# sensors.net
KiCad netlist of a schematic drawn in Altium Designer
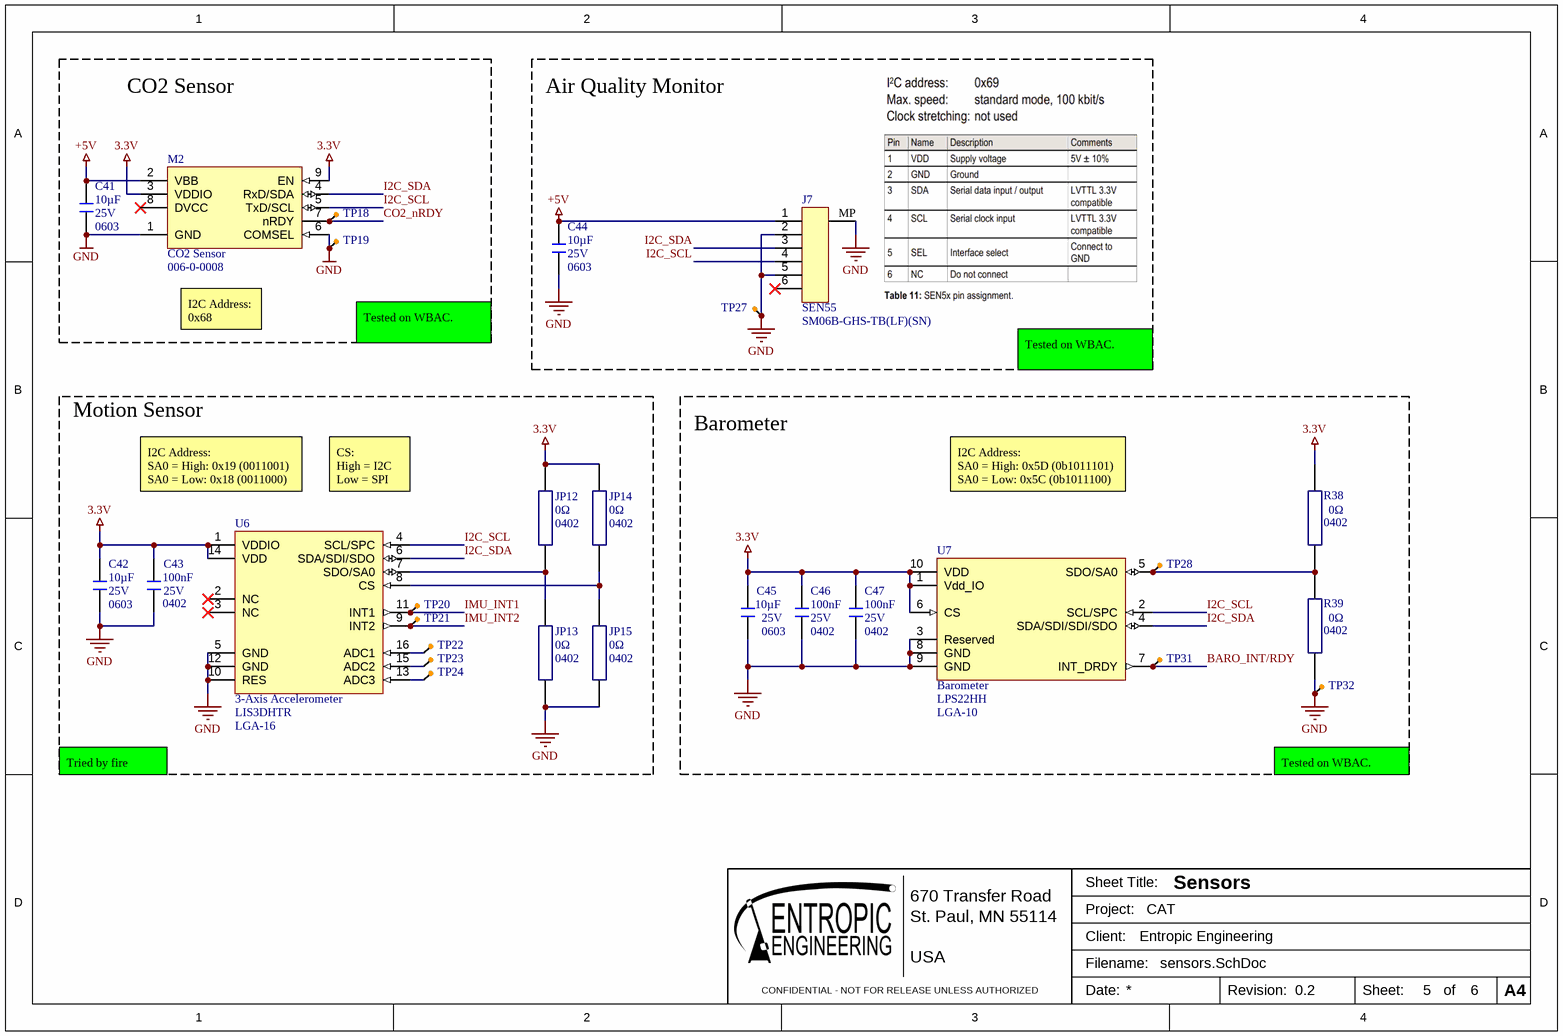
[diagram p0: sensors.SchDoc]

(export (version "E")
  (design (tool "Eeschema 10.0.6"))
  (components
    (comp (ref "C41")
      (value "10µF")
      (footprint "0603_capacitor")
      (description "10 µF, 25 V, X5R, 0603 Chip capacitor")
      (fields
        (field (name "MANUFACTURER") "Samsung")
        (field (name "CASE/PACKAGE") "0603")
        (field (name "TOLERANCE") "20%")
        (field (name "VOLTAGE RATING") "25V")
      )
      (libsource (lib "cat") (part "CL10A106MA8NRNC"))
    )
    (comp (ref "C42")
      (value "10µF")
      (footprint "0603_capacitor")
      (description "10 µF, 25 V, X5R, 0603 Chip capacitor")
      (fields
        (field (name "MANUFACTURER") "Samsung")
        (field (name "CASE/PACKAGE") "0603")
        (field (name "TOLERANCE") "20%")
        (field (name "VOLTAGE RATING") "25V")
      )
      (libsource (lib "cat") (part "CL10A106MA8NRNC"))
    )
    (comp (ref "C43")
      (value "GRM155R71E104KE14D")
      (footprint "0402_capacitor")
      (description "100 nF, 25 V, X7R, 0402 Chip capacitor")
      (fields
        (field (name "MANUFACTURER") "Murata")
        (field (name "TOLERANCE") "10%")
        (field (name "CASE CODE (IMPERIAL)") "0402")
        (field (name "VOLTAGE") "25V")
        (field (name "CAPACITANCE") "100nF")
      )
      (libsource (lib "cat") (part "GRM155R71E104KE14D"))
    )
    (comp (ref "C44")
      (value "10µF")
      (footprint "0603_capacitor")
      (description "10 µF, 25 V, X5R, 0603 Chip capacitor")
      (fields
        (field (name "MANUFACTURER") "Samsung")
        (field (name "CASE/PACKAGE") "0603")
        (field (name "TOLERANCE") "20%")
        (field (name "VOLTAGE RATING") "25V")
      )
      (libsource (lib "cat") (part "CL10A106MA8NRNC"))
    )
    (comp (ref "C45")
      (value "10µF")
      (footprint "0603_capacitor")
      (description "10 µF, 25 V, X5R, 0603 Chip capacitor")
      (fields
        (field (name "MANUFACTURER") "Samsung")
        (field (name "MANUFACTURER PART NUMBER") "CL10A106MA8NRNC")
        (field (name "VOLTAGE RATING") "25V")
        (field (name "CASE/PACKAGE") "0603")
      )
      (libsource (lib "cat") (part "CL10A106MA8NRNC"))
    )
    (comp (ref "C46")
      (value "GRM155R71E104KE14D")
      (footprint "0402_capacitor")
      (description "100 nF, 25 V, X7R, 0402 Chip capacitor")
      (fields
        (field (name "MANUFACTURER") "Murata")
        (field (name "TOLERANCE") "10%")
        (field (name "CASE CODE (IMPERIAL)") "0402")
        (field (name "VOLTAGE") "25V")
        (field (name "CAPACITANCE") "100nF")
      )
      (libsource (lib "cat") (part "GRM155R71E104KE14D"))
    )
    (comp (ref "C47")
      (value "GRM155R71E104KE14D")
      (footprint "0402_capacitor")
      (description "100 nF, 25 V, X7R, 0402 Chip capacitor")
      (fields
        (field (name "MANUFACTURER") "Murata")
        (field (name "TOLERANCE") "10%")
        (field (name "CASE CODE (IMPERIAL)") "0402")
        (field (name "VOLTAGE") "25V")
        (field (name "CAPACITANCE") "100nF")
      )
      (libsource (lib "cat") (part "GRM155R71E104KE14D"))
    )
    (comp (ref "J7")
      (value "SEN55")
      (footprint "SM06B-GHS-TB")
      (description "6-Pin JST GH header, 1.25mm pitch, SMD right angle")
      (fields
        (field (name "MANUFACTURER") "JST")
        (field (name "MANUFACTURER PART NUMBER") "SM06B-GHS-TB(LF)(SN)")
      )
      (libsource (lib "cat") (part "SM06B-GHS-TB(LF)(SN)"))
    )
    (comp (ref "JP12")
      (value "0Ω")
      (footprint "0402_resistor")
      (description "0 Ω, 0402 Chip resistor (jumper)")
      (fields
        (field (name "MANUFACTURER") "Yageo")
        (field (name "MANUFACTURER PART NUMBER") "RC0402FR-070RL")
        (field (name "CASE/PACKAGE") "0402")
      )
      (libsource (lib "cat") (part "RC0402FR-070RL"))
    )
    (comp (ref "JP13")
      (value "0Ω")
      (footprint "0402_resistor")
      (description "0 Ω, 0402 Chip resistor (jumper)")
      (fields
        (field (name "MANUFACTURER") "Yageo")
        (field (name "MANUFACTURER PART NUMBER") "RC0402FR-070RL")
        (field (name "CASE/PACKAGE") "0402")
      )
      (libsource (lib "cat") (part "RC0402FR-070RL"))
    )
    (comp (ref "JP14")
      (value "0Ω")
      (footprint "0402_resistor")
      (description "0 Ω, 0402 Chip resistor (jumper)")
      (fields
        (field (name "MANUFACTURER") "Yageo")
        (field (name "MANUFACTURER PART NUMBER") "RC0402FR-070RL")
        (field (name "CASE/PACKAGE") "0402")
      )
      (libsource (lib "cat") (part "RC0402FR-070RL"))
    )
    (comp (ref "JP15")
      (value "0Ω")
      (footprint "0402_resistor")
      (description "0 Ω, 0402 Chip resistor (jumper)")
      (fields
        (field (name "MANUFACTURER") "Yageo")
        (field (name "MANUFACTURER PART NUMBER") "RC0402FR-070RL")
        (field (name "CASE/PACKAGE") "0402")
      )
      (libsource (lib "cat") (part "RC0402FR-070RL"))
    )
    (comp (ref "M2")
      (value "CO2 Sensor")
      (footprint "006-0-0008")
      (description "Sensair CO2 sensor")
      (fields (field (name "MANUFACTURER PART NUMBER") "006-0-0008"))
      (libsource (lib "cat") (part "006-0-0008"))
    )
    (comp (ref "R38")
      (value "0Ω")
      (footprint "0402_resistor")
      (description "0 Ω, 0402 Chip resistor (jumper)")
      (fields
        (field (name "MANUFACTURER") "Yageo")
        (field (name "MANUFACTURER PART NUMBER") "RC0402FR-070RL")
        (field (name "CASE/PACKAGE") "0402")
      )
      (libsource (lib "cat") (part "RC0402FR-070RL"))
    )
    (comp (ref "R39")
      (value "0Ω")
      (footprint "0402_resistor")
      (description "0 Ω, 0402 Chip resistor (jumper)")
      (fields
        (field (name "MANUFACTURER") "Yageo")
        (field (name "MANUFACTURER PART NUMBER") "RC0402FR-070RL")
        (field (name "CASE/PACKAGE") "0402")
      )
      (libsource (lib "cat") (part "RC0402FR-070RL"))
    )
    (comp (ref "TP18")
      (value "CO2_nRDY")
      (footprint "test_point-1")
      (description "Test point")
      (libsource (lib "cat") (part "test_point-1"))
    )
    (comp (ref "TP19")
      (value "SENSOR_SDA")
      (footprint "test_point-1")
      (description "Test point")
      (libsource (lib "cat") (part "test_point-1"))
    )
    (comp (ref "TP20")
      (value "test_point-1")
      (footprint "test_point-1")
      (description "Test point")
      (libsource (lib "cat") (part "test_point-1"))
    )
    (comp (ref "TP21")
      (value "test_point-1")
      (footprint "test_point-1")
      (description "Test point")
      (libsource (lib "cat") (part "test_point-1"))
    )
    (comp (ref "TP22")
      (value "test_point-1")
      (footprint "test_point-1")
      (description "Test point")
      (libsource (lib "cat") (part "test_point-1"))
    )
    (comp (ref "TP23")
      (value "test_point-1")
      (footprint "test_point-1")
      (description "Test point")
      (libsource (lib "cat") (part "test_point-1"))
    )
    (comp (ref "TP24")
      (value "test_point-1")
      (footprint "test_point-1")
      (description "Test point")
      (libsource (lib "cat") (part "test_point-1"))
    )
    (comp (ref "TP27")
      (value "SENSOR_SDA")
      (footprint "test_point-1")
      (description "Test point")
      (libsource (lib "cat") (part "test_point-1"))
    )
    (comp (ref "TP28")
      (value "SENSOR_SDA")
      (footprint "test_point-1")
      (description "Test point")
      (libsource (lib "cat") (part "test_point-1"))
    )
    (comp (ref "TP31")
      (value "SENSOR_SCL")
      (footprint "test_point-1")
      (description "Test point")
      (libsource (lib "cat") (part "test_point-1"))
    )
    (comp (ref "TP32")
      (value "SENSOR_SDA")
      (footprint "test_point-1")
      (description "Test point")
      (libsource (lib "cat") (part "test_point-1"))
    )
    (comp (ref "U6")
      (value "3-Axis Accelerometer")
      (footprint "LGA50P300X300X100-16N")
      (description "3-Axis accelerometer, 16-bit, I2C/SPI, LGA-16")
      (fields
        (field (name "MANUFACTURER") "STMicroelectronics")
        (field (name "CASE/PACKAGE") "LGA-16")
        (field (name "MANUFACTURER PART NUMBER") "LIS3DHTR")
        (field (name "HOUSE_PART_NUMBER") "LIS3DHTR")
      )
      (libsource (lib "cat") (part "LIS3DHTR"))
    )
    (comp (ref "U7")
      (value "Barometer")
      (footprint "LPS22")
      (description "260-1260 hPa Absolute barometer, LGA-10")
      (fields
        (field (name "MANUFACTURER") "STMicroelectronics")
        (field (name "MANUFACTURER PART NUMBER") "LPS22HH")
        (field (name "PACKAGE") "LGA-10")
      )
      (libsource (lib "cat") (part "LPS22HH"))
    )
  )
  (nets
    (net (code "1") (name "+5V") (class "Default")
      (node (ref "C41") (pin "2") (pinfunction "2_2") (pintype "passive"))
      (node (ref "C44") (pin "2") (pinfunction "2_2") (pintype "passive"))
      (node (ref "J7") (pin "1") (pintype "passive"))
      (node (ref "M2") (pin "2") (pinfunction "VBB_2") (pintype "power_in"))
    )
    (net (code "2") (name "/BARO_INT{slash}RDY") (class "Default")
      (node (ref "TP31") (pin "1") (pinfunction "1_1") (pintype "passive"))
      (node (ref "U7") (pin "7") (pinfunction "INT_DRDY_7") (pintype "output"))
    )
    (net (code "3") (name "/CO2_nRDY") (class "Default")
      (node (ref "M2") (pin "7") (pinfunction "nRDY_7") (pintype "open_collector"))
      (node (ref "TP18") (pin "1") (pinfunction "1_1") (pintype "passive"))
    )
    (net (code "4") (name "/I2C_SCL") (class "Default")
      (node (ref "J7") (pin "4") (pintype "passive"))
      (node (ref "M2") (pin "5") (pinfunction "TxD/SCL_5") (pintype "bidirectional"))
      (node (ref "U6") (pin "4") (pinfunction "SCL/SPC_4") (pintype "input"))
      (node (ref "U7") (pin "2") (pinfunction "SCL/SPC_2") (pintype "input"))
    )
    (net (code "5") (name "/I2C_SDA") (class "Default")
      (node (ref "J7") (pin "3") (pintype "passive"))
      (node (ref "M2") (pin "4") (pinfunction "RxD/SDA_4") (pintype "bidirectional"))
      (node (ref "U6") (pin "6") (pinfunction "SDA/SDI/SDO_6") (pintype "bidirectional"))
      (node (ref "U7") (pin "4") (pinfunction "SDA/SDI/SDI/SDO_4") (pintype "bidirectional"))
    )
    (net (code "6") (name "/IMU_INT1") (class "Default")
      (node (ref "TP20") (pin "1") (pinfunction "1_1") (pintype "passive"))
      (node (ref "U6") (pin "11") (pinfunction "INT1_11") (pintype "output"))
    )
    (net (code "7") (name "/IMU_INT2") (class "Default")
      (node (ref "TP21") (pin "1") (pinfunction "1_1") (pintype "passive"))
      (node (ref "U6") (pin "9") (pinfunction "INT2_9") (pintype "output"))
    )
    (net (code "8") (name "3.3V") (class "Default")
      (node (ref "C42") (pin "2") (pinfunction "2_2") (pintype "passive"))
      (node (ref "C43") (pin "2") (pinfunction "2_2") (pintype "passive"))
      (node (ref "C45") (pin "2") (pinfunction "2_2") (pintype "passive"))
      (node (ref "C46") (pin "2") (pinfunction "2_2") (pintype "passive"))
      (node (ref "C47") (pin "2") (pinfunction "2_2") (pintype "passive"))
      (node (ref "JP12") (pin "1") (pinfunction "1_1") (pintype "passive"))
      (node (ref "JP14") (pin "1") (pinfunction "1_1") (pintype "passive"))
      (node (ref "M2") (pin "3") (pinfunction "VDDIO_3") (pintype "power_in"))
      (node (ref "M2") (pin "9") (pinfunction "EN_9") (pintype "input"))
      (node (ref "R38") (pin "1") (pinfunction "1_1") (pintype "passive"))
      (node (ref "U6") (pin "1") (pinfunction "VDDIO_1") (pintype "power_in"))
      (node (ref "U6") (pin "14") (pinfunction "VDD_14") (pintype "power_in"))
      (node (ref "U7") (pin "1") (pinfunction "Vdd_IO_1") (pintype "power_in"))
      (node (ref "U7") (pin "10") (pinfunction "VDD_10") (pintype "power_in"))
      (node (ref "U7") (pin "6") (pinfunction "CS_6") (pintype "input"))
    )
    (net (code "9") (name "GND") (class "Default")
      (node (ref "C41") (pin "1") (pinfunction "1_1") (pintype "passive"))
      (node (ref "C42") (pin "1") (pinfunction "1_1") (pintype "passive"))
      (node (ref "C43") (pin "1") (pinfunction "1_1") (pintype "passive"))
      (node (ref "C44") (pin "1") (pinfunction "1_1") (pintype "passive"))
      (node (ref "C45") (pin "1") (pinfunction "1_1") (pintype "passive"))
      (node (ref "C46") (pin "1") (pinfunction "1_1") (pintype "passive"))
      (node (ref "C47") (pin "1") (pinfunction "1_1") (pintype "passive"))
      (node (ref "J7") (pin "2") (pintype "passive"))
      (node (ref "J7") (pin "5") (pintype "passive"))
      (node (ref "J7") (pin "MP") (pintype "passive"))
      (node (ref "JP13") (pin "2") (pinfunction "2_2") (pintype "passive"))
      (node (ref "JP15") (pin "2") (pinfunction "2_2") (pintype "passive"))
      (node (ref "M2") (pin "1") (pinfunction "GND_1") (pintype "power_in"))
      (node (ref "M2") (pin "6") (pinfunction "COMSEL_6") (pintype "input"))
      (node (ref "R39") (pin "2") (pinfunction "2_2") (pintype "passive"))
      (node (ref "TP19") (pin "1") (pinfunction "1_1") (pintype "passive"))
      (node (ref "TP27") (pin "1") (pinfunction "1_1") (pintype "passive"))
      (node (ref "TP32") (pin "1") (pinfunction "1_1") (pintype "passive"))
      (node (ref "U6") (pin "10") (pinfunction "RES_10") (pintype "power_in"))
      (node (ref "U6") (pin "12") (pinfunction "GND_12") (pintype "power_in"))
      (node (ref "U6") (pin "5") (pinfunction "GND_5") (pintype "power_in"))
      (node (ref "U7") (pin "3") (pinfunction "Reserved_3") (pintype "power_in"))
      (node (ref "U7") (pin "8") (pinfunction "GND_8") (pintype "power_in"))
      (node (ref "U7") (pin "9") (pinfunction "GND_9") (pintype "power_in"))
    )
    (net (code "10") (name "Net-(U6-ADC1)") (class "Default")
      (node (ref "TP22") (pin "1") (pinfunction "1_1") (pintype "passive"))
      (node (ref "U6") (pin "16") (pinfunction "ADC1_16") (pintype "input"))
    )
    (net (code "11") (name "Net-(U6-ADC2)") (class "Default")
      (node (ref "TP23") (pin "1") (pinfunction "1_1") (pintype "passive"))
      (node (ref "U6") (pin "15") (pinfunction "ADC2_15") (pintype "input"))
    )
    (net (code "12") (name "Net-(U6-ADC3)") (class "Default")
      (node (ref "TP24") (pin "1") (pinfunction "1_1") (pintype "passive"))
      (node (ref "U6") (pin "13") (pinfunction "ADC3_13") (pintype "input"))
    )
    (net (code "13") (name "Net-(U6-CS)") (class "Default")
      (node (ref "JP14") (pin "2") (pinfunction "2_2") (pintype "passive"))
      (node (ref "JP15") (pin "1") (pinfunction "1_1") (pintype "passive"))
      (node (ref "U6") (pin "8") (pinfunction "CS_8") (pintype "input"))
    )
    (net (code "14") (name "Net-(U6-SDO{slash}SA0)") (class "Default")
      (node (ref "JP12") (pin "2") (pinfunction "2_2") (pintype "passive"))
      (node (ref "JP13") (pin "1") (pinfunction "1_1") (pintype "passive"))
      (node (ref "U6") (pin "7") (pinfunction "SDO/SA0_7") (pintype "bidirectional"))
    )
    (net (code "15") (name "Net-(U7-SDO{slash}SA0)") (class "Default")
      (node (ref "R38") (pin "2") (pinfunction "2_2") (pintype "passive"))
      (node (ref "R39") (pin "1") (pinfunction "1_1") (pintype "passive"))
      (node (ref "TP28") (pin "1") (pinfunction "1_1") (pintype "passive"))
      (node (ref "U7") (pin "5") (pinfunction "SDO/SA0_5") (pintype "bidirectional"))
    )
    (net (code "16") (name "unconnected-(J7-Pad6)") (class "Default")
      (node (ref "J7") (pin "6") (pintype "passive+no_connect"))
    )
    (net (code "17") (name "unconnected-(M2-DVCC-Pad8)") (class "Default")
      (node (ref "M2") (pin "8") (pinfunction "DVCC_8") (pintype "power_in+no_connect"))
    )
    (net (code "18") (name "unconnected-(U6-NC-Pad2)") (class "Default")
      (node (ref "U6") (pin "2") (pinfunction "NC_2") (pintype "power_in+no_connect"))
    )
    (net (code "19") (name "unconnected-(U6-NC-Pad3)") (class "Default")
      (node (ref "U6") (pin "3") (pinfunction "NC_3") (pintype "power_in+no_connect"))
    )
  )
)
